# Connectors.net
KiCad netlist of a schematic drawn in Altium Designer
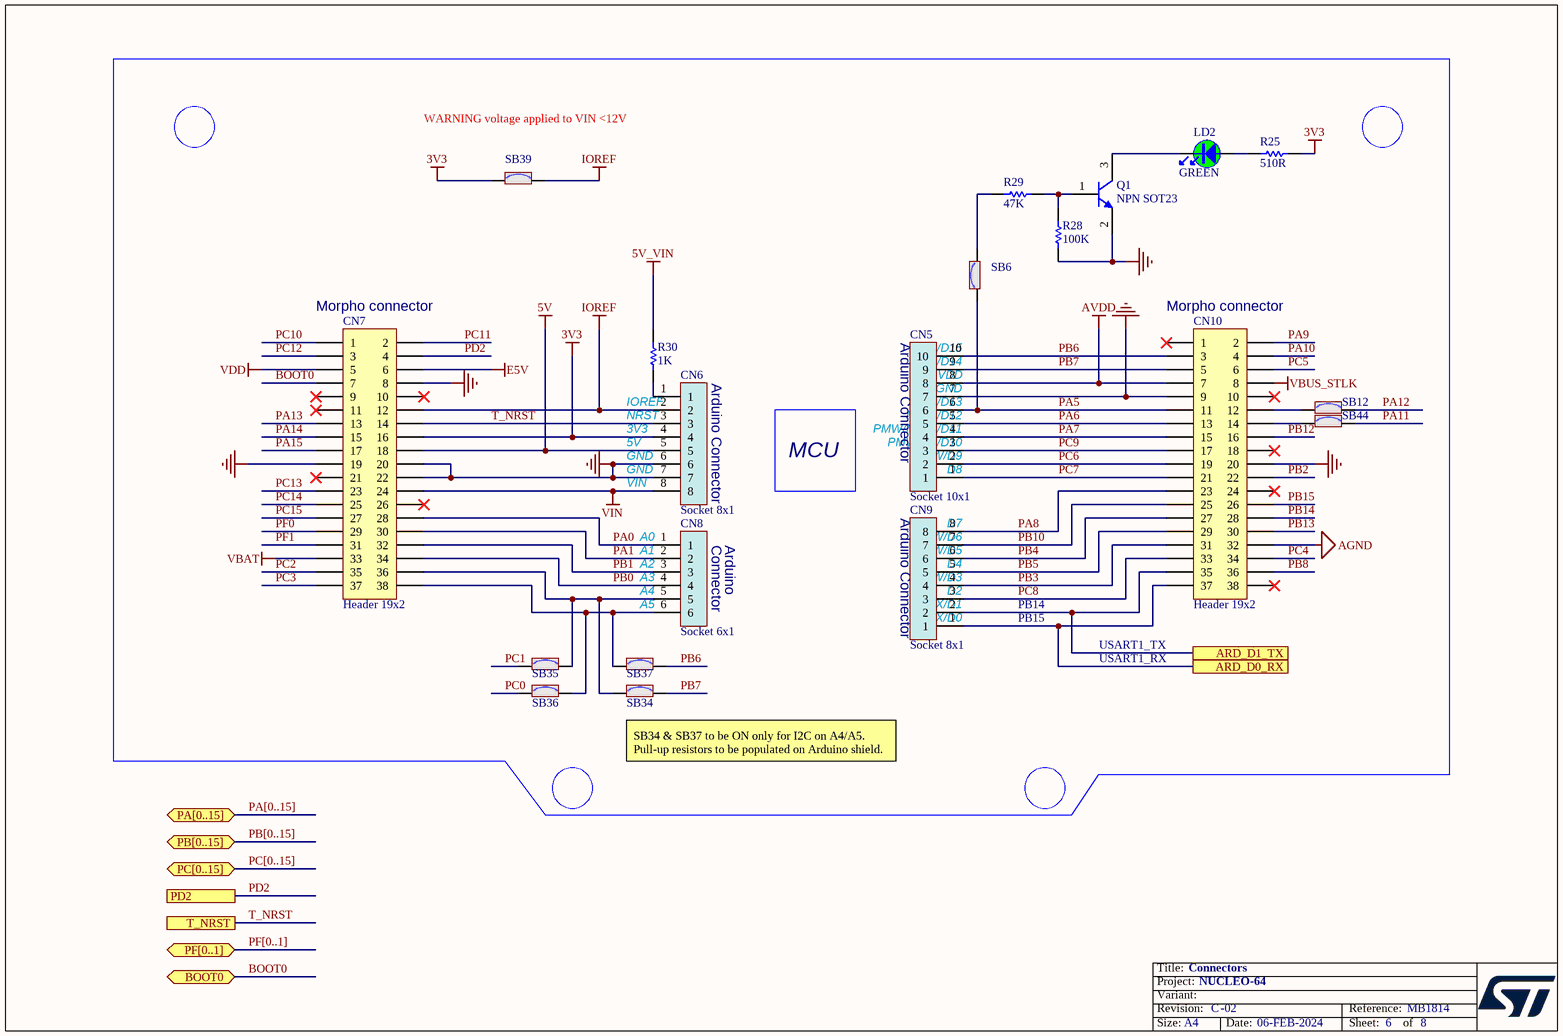
[diagram p0: Connectors.SchDoc]

(export (version "E")
  (design (tool "Eeschema 10.0.6"))
  (components
    (comp (ref "CN5")
      (value "Socket 10x1")
      (footprint "CON_SAMTEC_SSQ-110-03-F-S")
      (description "Socket, 10x1, 2.54mm, VR, TH, T=8.51mm/10mm")
      (fields (field (name "INTERNAL_PART_NUMBER") "MCD-02625") (field (name "MANUFACTURER") "SAMTEC"))
      (libsource (lib "MCD_PARTS_database") (part "Socket 10x1"))
    )
    (comp (ref "CN6")
      (value "Socket 8x1")
      (footprint "CON_SAMTEC_SSQ-108-03-F-S")
      (description "Socket, 8x1, 2.54mm, VR, TH, T=8.51mm/10mm")
      (fields (field (name "INTERNAL_PART_NUMBER") "MCD-02624") (field (name "MANUFACTURER") "SAMTEC"))
      (libsource (lib "MCD_PARTS_database") (part "Socket 8x1"))
    )
    (comp (ref "CN7")
      (value "Header 19x2")
      (footprint "CON_SAMTEC_TSW-119-09-X-D")
      (description "Header, 19x2, 2,54mm, VR, TH, Height 5.84mm/10.16mm")
      (fields
        (field (name "INTERNAL_PART_NUMBER") "MCD-00213")
        (field (name "MANUFACTURER_PART_NUMBER") "TSW-119-09-x-D")
        (field (name "PROVIDED_BY") "SUBCO")
      )
      (libsource (lib "MCD_PARTS_database") (part "Header 19x2"))
    )
    (comp (ref "CN8")
      (value "Socket 6x1")
      (footprint "CON_SAMTEC_SSQ-106-03-F-S")
      (description "Socket, 6x1, 2.54mm, VR, TH, T=8.51mm/10mm")
      (fields (field (name "INTERNAL_PART_NUMBER") "MCD-02623") (field (name "MANUFACTURER") "SAMTEC"))
      (libsource (lib "MCD_PARTS_database") (part "Socket 6x1"))
    )
    (comp (ref "CN9")
      (value "Socket 8x1")
      (footprint "CON_SAMTEC_SSQ-108-03-F-S")
      (description "Socket, 8x1, 2.54mm, VR, TH, T=8.51mm/10mm")
      (fields (field (name "INTERNAL_PART_NUMBER") "MCD-02624") (field (name "MANUFACTURER") "SAMTEC"))
      (libsource (lib "") (part "Socket 8x1_1"))
    )
    (comp (ref "CN10")
      (value "Header 19x2")
      (footprint "CON_SAMTEC_TSW-119-09-X-D")
      (description "Header, 19x2, 2,54mm, VR, TH, Height 5.84mm/10.16mm")
      (fields
        (field (name "INTERNAL_PART_NUMBER") "MCD-00213")
        (field (name "MANUFACTURER_PART_NUMBER") "TSW-119-09-x-D")
        (field (name "PROVIDED_BY") "SUBCO")
      )
      (libsource (lib "MCD_PARTS_database") (part "Header 19x2"))
    )
    (comp (ref "LD2")
      (value "GREEN")
      (footprint "LED_0603_OSRAM_LG-Q396-PS-35_GREEN_1A2K_H0P4")
      (description "LED Green, 0603 SMD, Forward Voltage Typ=2V, Max=2.5V")
      (fields
        (field (name "INTERNAL_PART_NUMBER") "MCD-00588")
        (field (name "MANUFACTURER_PART_NUMBER") "LG Q396-PS-35")
        (field (name "PROVIDED_BY") "SUBCO")
      )
      (libsource (lib "MCD_PARTS_database") (part "LED_green"))
    )
    (comp (ref "Q1")
      (value "NPN SOT23")
      (footprint "NPN_SOT23")
      (description "NPN Bipolar Transistor")
      (fields
        (field (name "INTERNAL_PART_NUMBER") "MCD-00073")
        (field (name "MANUFACTURER_PART_NUMBER") "BSR14")
        (field (name "PROVIDED_BY") "SUBCO")
      )
      (libsource (lib "MCD_PARTS_database") (part "9013-SOT23"))
    )
    (comp (ref "R25")
      (value "510R")
      (footprint "R0603")
      (description "Resistor,510R,0603,1%,1/10W")
      (fields
        (field (name "INTERNAL_PART_NUMBER") "MCD-00225")
        (field (name "MANUFACTURER_PART_NUMBER") "RC0603FR-07510RL")
        (field (name "PROVIDED_BY") "SUBCO")
      )
      (libsource (lib "MCD_PARTS_database") (part "Resistor"))
    )
    (comp (ref "R28")
      (value "100K")
      (footprint "R0603")
      (description "Resistor,100K,0603,1%,1/10W")
      (fields
        (field (name "INTERNAL_PART_NUMBER") "MCD-00223")
        (field (name "MANUFACTURER_PART_NUMBER") "RC0603FR-07100KL")
        (field (name "PROVIDED_BY") "Subcon")
      )
      (libsource (lib "MCD_PARTS_database") (part "Resistor"))
    )
    (comp (ref "R29")
      (value "47K")
      (footprint "R0603")
      (description "Resistor,47K,0603,1%,1/10W")
      (fields
        (field (name "INTERNAL_PART_NUMBER") "MCD-00222")
        (field (name "MANUFACTURER_PART_NUMBER") "RC0603FR-0747KL")
        (field (name "PROVIDED_BY") "SUBCO")
      )
      (libsource (lib "MCD_PARTS_database") (part "Resistor"))
    )
    (comp (ref "R30")
      (value "1K")
      (footprint "R0603")
      (description "Resistor,1K,0603,1%,1/10W")
      (fields
        (field (name "INTERNAL_PART_NUMBER") "MCD-00070")
        (field (name "MANUFACTURER_PART_NUMBER") "RC0603FR-071KL")
        (field (name "PROVIDED_BY") "Subcon")
      )
      (libsource (lib "MCD_PARTS_database") (part "Resistor"))
    )
    (comp (ref "SB6")
      (value "~")
      (footprint "SOLDER-BRIDGE_R0603-0R")
      (description "Solder Bridge ON")
      (fields
        (field (name "INTERNAL_PART_NUMBER") "MCD-00071")
        (field (name "MANUFACTURER_PART_NUMBER") "RC0603JR-070RL")
        (field (name "PROVIDED_BY") "SUBCO")
      )
      (libsource (lib "") (part "SB_ON_1"))
    )
    (comp (ref "SB12")
      (value "~")
      (footprint "SOLDER-BRIDGE_R0603-0R")
      (description "Solder Bridge ON")
      (fields
        (field (name "INTERNAL_PART_NUMBER") "MCD-00071")
        (field (name "MANUFACTURER_PART_NUMBER") "RC0603JR-070RL")
        (field (name "PROVIDED_BY") "SUBCO")
      )
      (libsource (lib "MCD_PARTS_database") (part "SB_ON"))
    )
    (comp (ref "SB34")
      (value "~")
      (footprint "SOLDER-BRIDGE_R0603-0R")
      (description "Solder Bridge ON")
      (fields
        (field (name "INTERNAL_PART_NUMBER") "MCD-00071")
        (field (name "MANUFACTURER_PART_NUMBER") "RC0603JR-070RL")
        (field (name "PROVIDED_BY") "SUBCO")
      )
      (libsource (lib "MCD_PARTS_database") (part "SB_ON"))
    )
    (comp (ref "SB35")
      (value "~")
      (footprint "SOLDER-BRIDGE_R0603-0R")
      (description "Solder Bridge ON")
      (fields
        (field (name "INTERNAL_PART_NUMBER") "MCD-00071")
        (field (name "MANUFACTURER_PART_NUMBER") "RC0603JR-070RL")
        (field (name "PROVIDED_BY") "SUBCO")
      )
      (libsource (lib "MCD_PARTS_database") (part "SB_ON"))
    )
    (comp (ref "SB36")
      (value "~")
      (footprint "SOLDER-BRIDGE_R0603-0R")
      (description "Solder Bridge ON")
      (fields
        (field (name "INTERNAL_PART_NUMBER") "MCD-00071")
        (field (name "MANUFACTURER_PART_NUMBER") "RC0603JR-070RL")
        (field (name "PROVIDED_BY") "SUBCO")
      )
      (libsource (lib "MCD_PARTS_database") (part "SB_ON"))
    )
    (comp (ref "SB37")
      (value "~")
      (footprint "SOLDER-BRIDGE_R0603-0R")
      (description "Solder Bridge ON")
      (fields
        (field (name "INTERNAL_PART_NUMBER") "MCD-00071")
        (field (name "MANUFACTURER_PART_NUMBER") "RC0603JR-070RL")
        (field (name "PROVIDED_BY") "SUBCO")
      )
      (libsource (lib "MCD_PARTS_database") (part "SB_ON"))
    )
    (comp (ref "SB39")
      (value "~")
      (footprint "SOLDER-BRIDGE_R0603-0R")
      (description "Solder Bridge ON")
      (fields
        (field (name "INTERNAL_PART_NUMBER") "MCD-00071")
        (field (name "MANUFACTURER_PART_NUMBER") "RC0603JR-070RL")
        (field (name "PROVIDED_BY") "SUBCO")
      )
      (libsource (lib "MCD_PARTS_database") (part "SB_ON"))
    )
    (comp (ref "SB44")
      (value "~")
      (footprint "SOLDER-BRIDGE_R0603-0R")
      (description "Solder Bridge ON")
      (fields
        (field (name "INTERNAL_PART_NUMBER") "MCD-00071")
        (field (name "MANUFACTURER_PART_NUMBER") "RC0603JR-070RL")
        (field (name "PROVIDED_BY") "SUBCO")
      )
      (libsource (lib "MCD_PARTS_database") (part "SB_ON"))
    )
  )
  (nets
    (net (code "6") (name "/ARD_D0_RX") (class "Default")
      (node (ref "CN10") (pin "37") (pinfunction "37_37") (pintype "passive"))
      (node (ref "CN9") (pin "1") (pinfunction "1_1") (pintype "passive"))
    )
    (net (code "7") (name "/ARD_D1_TX") (class "Default")
      (node (ref "CN10") (pin "35") (pinfunction "35_35") (pintype "passive"))
      (node (ref "CN9") (pin "2") (pinfunction "2_2") (pintype "passive"))
    )
    (net (code "8") (name "/BOOT0") (class "Default")
      (node (ref "CN7") (pin "7") (pinfunction "7_7") (pintype "passive"))
    )
    (net (code "9") (name "/PA0") (class "Default")
      (node (ref "CN7") (pin "28") (pinfunction "28_28") (pintype "passive"))
      (node (ref "CN8") (pin "1") (pinfunction "1_1") (pintype "passive"))
    )
    (net (code "10") (name "/PA1") (class "Default")
      (node (ref "CN7") (pin "30") (pinfunction "30_30") (pintype "passive"))
      (node (ref "CN8") (pin "2") (pinfunction "2_2") (pintype "passive"))
    )
    (net (code "11") (name "/PA5") (class "Default")
      (node (ref "CN10") (pin "11") (pinfunction "11_11") (pintype "passive"))
      (node (ref "CN5") (pin "6") (pinfunction "6_6") (pintype "passive"))
      (node (ref "SB6") (pin "1") (pinfunction "1_1") (pintype "passive"))
    )
    (net (code "12") (name "/PA6") (class "Default")
      (node (ref "CN10") (pin "13") (pinfunction "13_13") (pintype "passive"))
      (node (ref "CN5") (pin "5") (pinfunction "5_5") (pintype "passive"))
    )
    (net (code "13") (name "/PA7") (class "Default")
      (node (ref "CN10") (pin "15") (pinfunction "15_15") (pintype "passive"))
      (node (ref "CN5") (pin "4") (pinfunction "4_4") (pintype "passive"))
    )
    (net (code "14") (name "/PA8") (class "Default")
      (node (ref "CN10") (pin "23") (pinfunction "23_23") (pintype "passive"))
      (node (ref "CN9") (pin "8") (pinfunction "8_8") (pintype "passive"))
    )
    (net (code "15") (name "/PA9") (class "Default")
      (node (ref "CN10") (pin "2") (pinfunction "2_2") (pintype "passive"))
    )
    (net (code "16") (name "/PA10") (class "Default")
      (node (ref "CN10") (pin "4") (pinfunction "4_4") (pintype "passive"))
    )
    (net (code "17") (name "/PA11") (class "Default")
      (node (ref "SB44") (pin "2") (pinfunction "2_2") (pintype "passive"))
    )
    (net (code "18") (name "/PA12") (class "Default")
      (node (ref "SB12") (pin "2") (pinfunction "2_2") (pintype "passive"))
    )
    (net (code "19") (name "/PA13") (class "Default")
      (node (ref "CN7") (pin "13") (pinfunction "13_13") (pintype "passive"))
    )
    (net (code "20") (name "/PA14") (class "Default")
      (node (ref "CN7") (pin "15") (pinfunction "15_15") (pintype "passive"))
    )
    (net (code "21") (name "/PA15") (class "Default")
      (node (ref "CN7") (pin "17") (pinfunction "17_17") (pintype "passive"))
    )
    (net (code "23") (name "/PB0") (class "Default")
      (node (ref "CN7") (pin "34") (pinfunction "34_34") (pintype "passive"))
      (node (ref "CN8") (pin "4") (pinfunction "4_4") (pintype "passive"))
    )
    (net (code "24") (name "/PB1") (class "Default")
      (node (ref "CN7") (pin "32") (pinfunction "32_32") (pintype "passive"))
      (node (ref "CN8") (pin "3") (pinfunction "3_3") (pintype "passive"))
    )
    (net (code "25") (name "/PB2") (class "Default")
      (node (ref "CN10") (pin "22") (pinfunction "22_22") (pintype "passive"))
    )
    (net (code "26") (name "/PB3") (class "Default")
      (node (ref "CN10") (pin "31") (pinfunction "31_31") (pintype "passive"))
      (node (ref "CN9") (pin "4") (pinfunction "4_4") (pintype "passive"))
    )
    (net (code "27") (name "/PB4") (class "Default")
      (node (ref "CN10") (pin "27") (pinfunction "27_27") (pintype "passive"))
      (node (ref "CN9") (pin "6") (pinfunction "6_6") (pintype "passive"))
    )
    (net (code "28") (name "/PB5") (class "Default")
      (node (ref "CN10") (pin "29") (pinfunction "29_29") (pintype "passive"))
      (node (ref "CN9") (pin "5") (pinfunction "5_5") (pintype "passive"))
    )
    (net (code "29") (name "/PB6") (class "Default")
      (node (ref "CN10") (pin "3") (pinfunction "3_3") (pintype "passive"))
      (node (ref "CN5") (pin "10") (pinfunction "10_10") (pintype "passive"))
      (node (ref "SB37") (pin "2") (pinfunction "2_2") (pintype "passive"))
    )
    (net (code "30") (name "/PB7") (class "Default")
      (node (ref "CN10") (pin "5") (pinfunction "5_5") (pintype "passive"))
      (node (ref "CN5") (pin "9") (pinfunction "9_9") (pintype "passive"))
      (node (ref "SB34") (pin "2") (pinfunction "2_2") (pintype "passive"))
    )
    (net (code "31") (name "/PB8") (class "Default")
      (node (ref "CN10") (pin "36") (pinfunction "36_36") (pintype "passive"))
    )
    (net (code "32") (name "/PB10") (class "Default")
      (node (ref "CN10") (pin "25") (pinfunction "25_25") (pintype "passive"))
      (node (ref "CN9") (pin "7") (pinfunction "7_7") (pintype "passive"))
    )
    (net (code "33") (name "/PB12") (class "Default")
      (node (ref "CN10") (pin "16") (pinfunction "16_16") (pintype "passive"))
    )
    (net (code "34") (name "/PB13") (class "Default")
      (node (ref "CN10") (pin "30") (pinfunction "30_30") (pintype "passive"))
    )
    (net (code "35") (name "/PB14") (class "Default")
      (node (ref "CN10") (pin "28") (pinfunction "28_28") (pintype "passive"))
    )
    (net (code "36") (name "/PB15") (class "Default")
      (node (ref "CN10") (pin "26") (pinfunction "26_26") (pintype "passive"))
    )
    (net (code "38") (name "/PC0") (class "Default")
      (node (ref "SB36") (pin "1") (pinfunction "1_1") (pintype "passive"))
    )
    (net (code "39") (name "/PC1") (class "Default")
      (node (ref "SB35") (pin "1") (pinfunction "1_1") (pintype "passive"))
    )
    (net (code "40") (name "/PC2") (class "Default")
      (node (ref "CN7") (pin "35") (pinfunction "35_35") (pintype "passive"))
    )
    (net (code "41") (name "/PC3") (class "Default")
      (node (ref "CN7") (pin "37") (pinfunction "37_37") (pintype "passive"))
    )
    (net (code "42") (name "/PC4") (class "Default")
      (node (ref "CN10") (pin "34") (pinfunction "34_34") (pintype "passive"))
    )
    (net (code "43") (name "/PC5") (class "Default")
      (node (ref "CN10") (pin "6") (pinfunction "6_6") (pintype "passive"))
    )
    (net (code "44") (name "/PC6") (class "Default")
      (node (ref "CN10") (pin "19") (pinfunction "19_19") (pintype "passive"))
      (node (ref "CN5") (pin "2") (pinfunction "2_2") (pintype "passive"))
    )
    (net (code "45") (name "/PC7") (class "Default")
      (node (ref "CN10") (pin "21") (pinfunction "21_21") (pintype "passive"))
      (node (ref "CN5") (pin "1") (pinfunction "1_1") (pintype "passive"))
    )
    (net (code "46") (name "/PC8") (class "Default")
      (node (ref "CN10") (pin "33") (pinfunction "33_33") (pintype "passive"))
      (node (ref "CN9") (pin "3") (pinfunction "3_3") (pintype "passive"))
    )
    (net (code "47") (name "/PC9") (class "Default")
      (node (ref "CN10") (pin "17") (pinfunction "17_17") (pintype "passive"))
      (node (ref "CN5") (pin "3") (pinfunction "3_3") (pintype "passive"))
    )
    (net (code "48") (name "/PC10") (class "Default")
      (node (ref "CN7") (pin "1") (pinfunction "1_1") (pintype "passive"))
    )
    (net (code "49") (name "/PC11") (class "Default")
      (node (ref "CN7") (pin "2") (pinfunction "2_2") (pintype "passive"))
    )
    (net (code "50") (name "/PC12") (class "Default")
      (node (ref "CN7") (pin "3") (pinfunction "3_3") (pintype "passive"))
    )
    (net (code "51") (name "/PC13") (class "Default")
      (node (ref "CN7") (pin "23") (pinfunction "23_23") (pintype "passive"))
    )
    (net (code "52") (name "/PC14") (class "Default")
      (node (ref "CN7") (pin "25") (pinfunction "25_25") (pintype "passive"))
    )
    (net (code "53") (name "/PC15") (class "Default")
      (node (ref "CN7") (pin "27") (pinfunction "27_27") (pintype "passive"))
    )
    (net (code "55") (name "/PD2") (class "Default")
      (node (ref "CN7") (pin "4") (pinfunction "4_4") (pintype "passive"))
    )
    (net (code "56") (name "/PF0") (class "Default")
      (node (ref "CN7") (pin "29") (pinfunction "29_29") (pintype "passive"))
    )
    (net (code "57") (name "/PF1") (class "Default")
      (node (ref "CN7") (pin "31") (pinfunction "31_31") (pintype "passive"))
    )
    (net (code "59") (name "/T_NRST") (class "Default")
      (node (ref "CN6") (pin "3") (pinfunction "3_3") (pintype "passive"))
      (node (ref "CN7") (pin "14") (pinfunction "14_14") (pintype "passive"))
    )
    (net (code "60") (name "3V3") (class "Default")
      (node (ref "CN6") (pin "4") (pinfunction "4_4") (pintype "passive"))
      (node (ref "CN7") (pin "16") (pinfunction "16_16") (pintype "passive"))
      (node (ref "R25") (pin "1") (pinfunction "1_1") (pintype "passive"))
      (node (ref "SB39") (pin "1") (pinfunction "1_1") (pintype "passive"))
    )
    (net (code "61") (name "5V") (class "Default")
      (node (ref "CN6") (pin "5") (pinfunction "5_5") (pintype "passive"))
      (node (ref "CN7") (pin "18") (pinfunction "18_18") (pintype "passive"))
    )
    (net (code "62") (name "5V_VIN") (class "Default")
      (node (ref "R30") (pin "2") (pinfunction "2_2") (pintype "passive"))
    )
    (net (code "63") (name "AGND") (class "Default")
      (node (ref "CN10") (pin "32") (pinfunction "32_32") (pintype "passive"))
    )
    (net (code "64") (name "AVDD") (class "Default")
      (node (ref "CN10") (pin "7") (pinfunction "7_7") (pintype "passive"))
      (node (ref "CN5") (pin "8") (pinfunction "8_8") (pintype "passive"))
    )
    (net (code "65") (name "E5V") (class "Default")
      (node (ref "CN7") (pin "6") (pinfunction "6_6") (pintype "passive"))
    )
    (net (code "66") (name "GND") (class "Default")
      (node (ref "CN10") (pin "20") (pinfunction "20_20") (pintype "passive"))
      (node (ref "CN10") (pin "9") (pinfunction "9_9") (pintype "passive"))
      (node (ref "CN5") (pin "7") (pinfunction "7_7") (pintype "passive"))
      (node (ref "CN6") (pin "6") (pinfunction "6_6") (pintype "passive"))
      (node (ref "CN6") (pin "7") (pinfunction "7_7") (pintype "passive"))
      (node (ref "CN7") (pin "19") (pinfunction "19_19") (pintype "passive"))
      (node (ref "CN7") (pin "20") (pinfunction "20_20") (pintype "passive"))
      (node (ref "CN7") (pin "22") (pinfunction "22_22") (pintype "passive"))
      (node (ref "CN7") (pin "8") (pinfunction "8_8") (pintype "passive"))
      (node (ref "Q1") (pin "2") (pinfunction "E_2") (pintype "passive"))
      (node (ref "R28") (pin "1") (pinfunction "1_1") (pintype "passive"))
    )
    (net (code "67") (name "IOREF") (class "Default")
      (node (ref "CN6") (pin "2") (pinfunction "2_2") (pintype "passive"))
      (node (ref "CN7") (pin "12") (pinfunction "12_12") (pintype "passive"))
      (node (ref "SB39") (pin "2") (pinfunction "2_2") (pintype "passive"))
    )
    (net (code "68") (name "Net-(CN6-Pad1)") (class "Default")
      (node (ref "CN6") (pin "1") (pinfunction "1_1") (pintype "passive"))
      (node (ref "R30") (pin "1") (pinfunction "1_1") (pintype "passive"))
    )
    (net (code "69") (name "Net-(CN7-Pad36)") (class "Default")
      (node (ref "CN7") (pin "36") (pinfunction "36_36") (pintype "passive"))
      (node (ref "CN8") (pin "5") (pinfunction "5_5") (pintype "passive"))
      (node (ref "SB34") (pin "1") (pinfunction "1_1") (pintype "passive"))
      (node (ref "SB35") (pin "2") (pinfunction "2_2") (pintype "passive"))
    )
    (net (code "70") (name "Net-(CN7-Pad38)") (class "Default")
      (node (ref "CN7") (pin "38") (pinfunction "38_38") (pintype "passive"))
      (node (ref "CN8") (pin "6") (pinfunction "6_6") (pintype "passive"))
      (node (ref "SB36") (pin "2") (pinfunction "2_2") (pintype "passive"))
      (node (ref "SB37") (pin "1") (pinfunction "1_1") (pintype "passive"))
    )
    (net (code "71") (name "Net-(CN10-Pad12)") (class "Default")
      (node (ref "CN10") (pin "12") (pinfunction "12_12") (pintype "passive"))
      (node (ref "SB12") (pin "1") (pinfunction "1_1") (pintype "passive"))
    )
    (net (code "72") (name "Net-(CN10-Pad14)") (class "Default")
      (node (ref "CN10") (pin "14") (pinfunction "14_14") (pintype "passive"))
      (node (ref "SB44") (pin "1") (pinfunction "1_1") (pintype "passive"))
    )
    (net (code "73") (name "Net-(LD2-Pad1)") (class "Default")
      (node (ref "LD2") (pin "1") (pintype "passive"))
      (node (ref "R25") (pin "2") (pinfunction "2_2") (pintype "passive"))
    )
    (net (code "74") (name "Net-(Q1-B)") (class "Default")
      (node (ref "Q1") (pin "1") (pinfunction "B_1") (pintype "passive"))
      (node (ref "R28") (pin "2") (pinfunction "2_2") (pintype "passive"))
      (node (ref "R29") (pin "2") (pinfunction "2_2") (pintype "passive"))
    )
    (net (code "75") (name "Net-(Q1-C)") (class "Default")
      (node (ref "LD2") (pin "2") (pintype "passive"))
      (node (ref "Q1") (pin "3") (pinfunction "C_3") (pintype "passive"))
    )
    (net (code "76") (name "Net-(R29-Pad1)") (class "Default")
      (node (ref "R29") (pin "1") (pinfunction "1_1") (pintype "passive"))
      (node (ref "SB6") (pin "2") (pinfunction "2_2") (pintype "passive"))
    )
    (net (code "77") (name "VBAT") (class "Default")
      (node (ref "CN7") (pin "33") (pinfunction "33_33") (pintype "passive"))
    )
    (net (code "78") (name "VBUS_STLK") (class "Default")
      (node (ref "CN10") (pin "8") (pinfunction "8_8") (pintype "passive"))
    )
    (net (code "79") (name "VDD") (class "Default")
      (node (ref "CN7") (pin "5") (pinfunction "5_5") (pintype "passive"))
    )
    (net (code "80") (name "VIN") (class "Default")
      (node (ref "CN6") (pin "8") (pinfunction "8_8") (pintype "passive"))
      (node (ref "CN7") (pin "24") (pinfunction "24_24") (pintype "passive"))
    )
    (net (code "81") (name "unconnected-(CN7-Pad9)") (class "Default")
      (node (ref "CN7") (pin "9") (pinfunction "9_9") (pintype "passive+no_connect"))
    )
    (net (code "82") (name "unconnected-(CN7-Pad10)") (class "Default")
      (node (ref "CN7") (pin "10") (pinfunction "10_10") (pintype "passive+no_connect"))
    )
    (net (code "83") (name "unconnected-(CN7-Pad11)") (class "Default")
      (node (ref "CN7") (pin "11") (pinfunction "11_11") (pintype "passive+no_connect"))
    )
    (net (code "84") (name "unconnected-(CN7-Pad21)") (class "Default")
      (node (ref "CN7") (pin "21") (pinfunction "21_21") (pintype "passive+no_connect"))
    )
    (net (code "85") (name "unconnected-(CN7-Pad26)") (class "Default")
      (node (ref "CN7") (pin "26") (pinfunction "26_26") (pintype "passive+no_connect"))
    )
    (net (code "86") (name "unconnected-(CN10-Pad1)") (class "Default")
      (node (ref "CN10") (pin "1") (pinfunction "1_1") (pintype "passive+no_connect"))
    )
    (net (code "87") (name "unconnected-(CN10-Pad10)") (class "Default")
      (node (ref "CN10") (pin "10") (pinfunction "10_10") (pintype "passive+no_connect"))
    )
    (net (code "88") (name "unconnected-(CN10-Pad18)") (class "Default")
      (node (ref "CN10") (pin "18") (pinfunction "18_18") (pintype "passive+no_connect"))
    )
    (net (code "89") (name "unconnected-(CN10-Pad24)") (class "Default")
      (node (ref "CN10") (pin "24") (pinfunction "24_24") (pintype "passive+no_connect"))
    )
    (net (code "90") (name "unconnected-(CN10-Pad38)") (class "Default")
      (node (ref "CN10") (pin "38") (pinfunction "38_38") (pintype "passive+no_connect"))
    )
  )
)
